# untitled.net
KiCad netlist of a schematic drawn in EAGLE
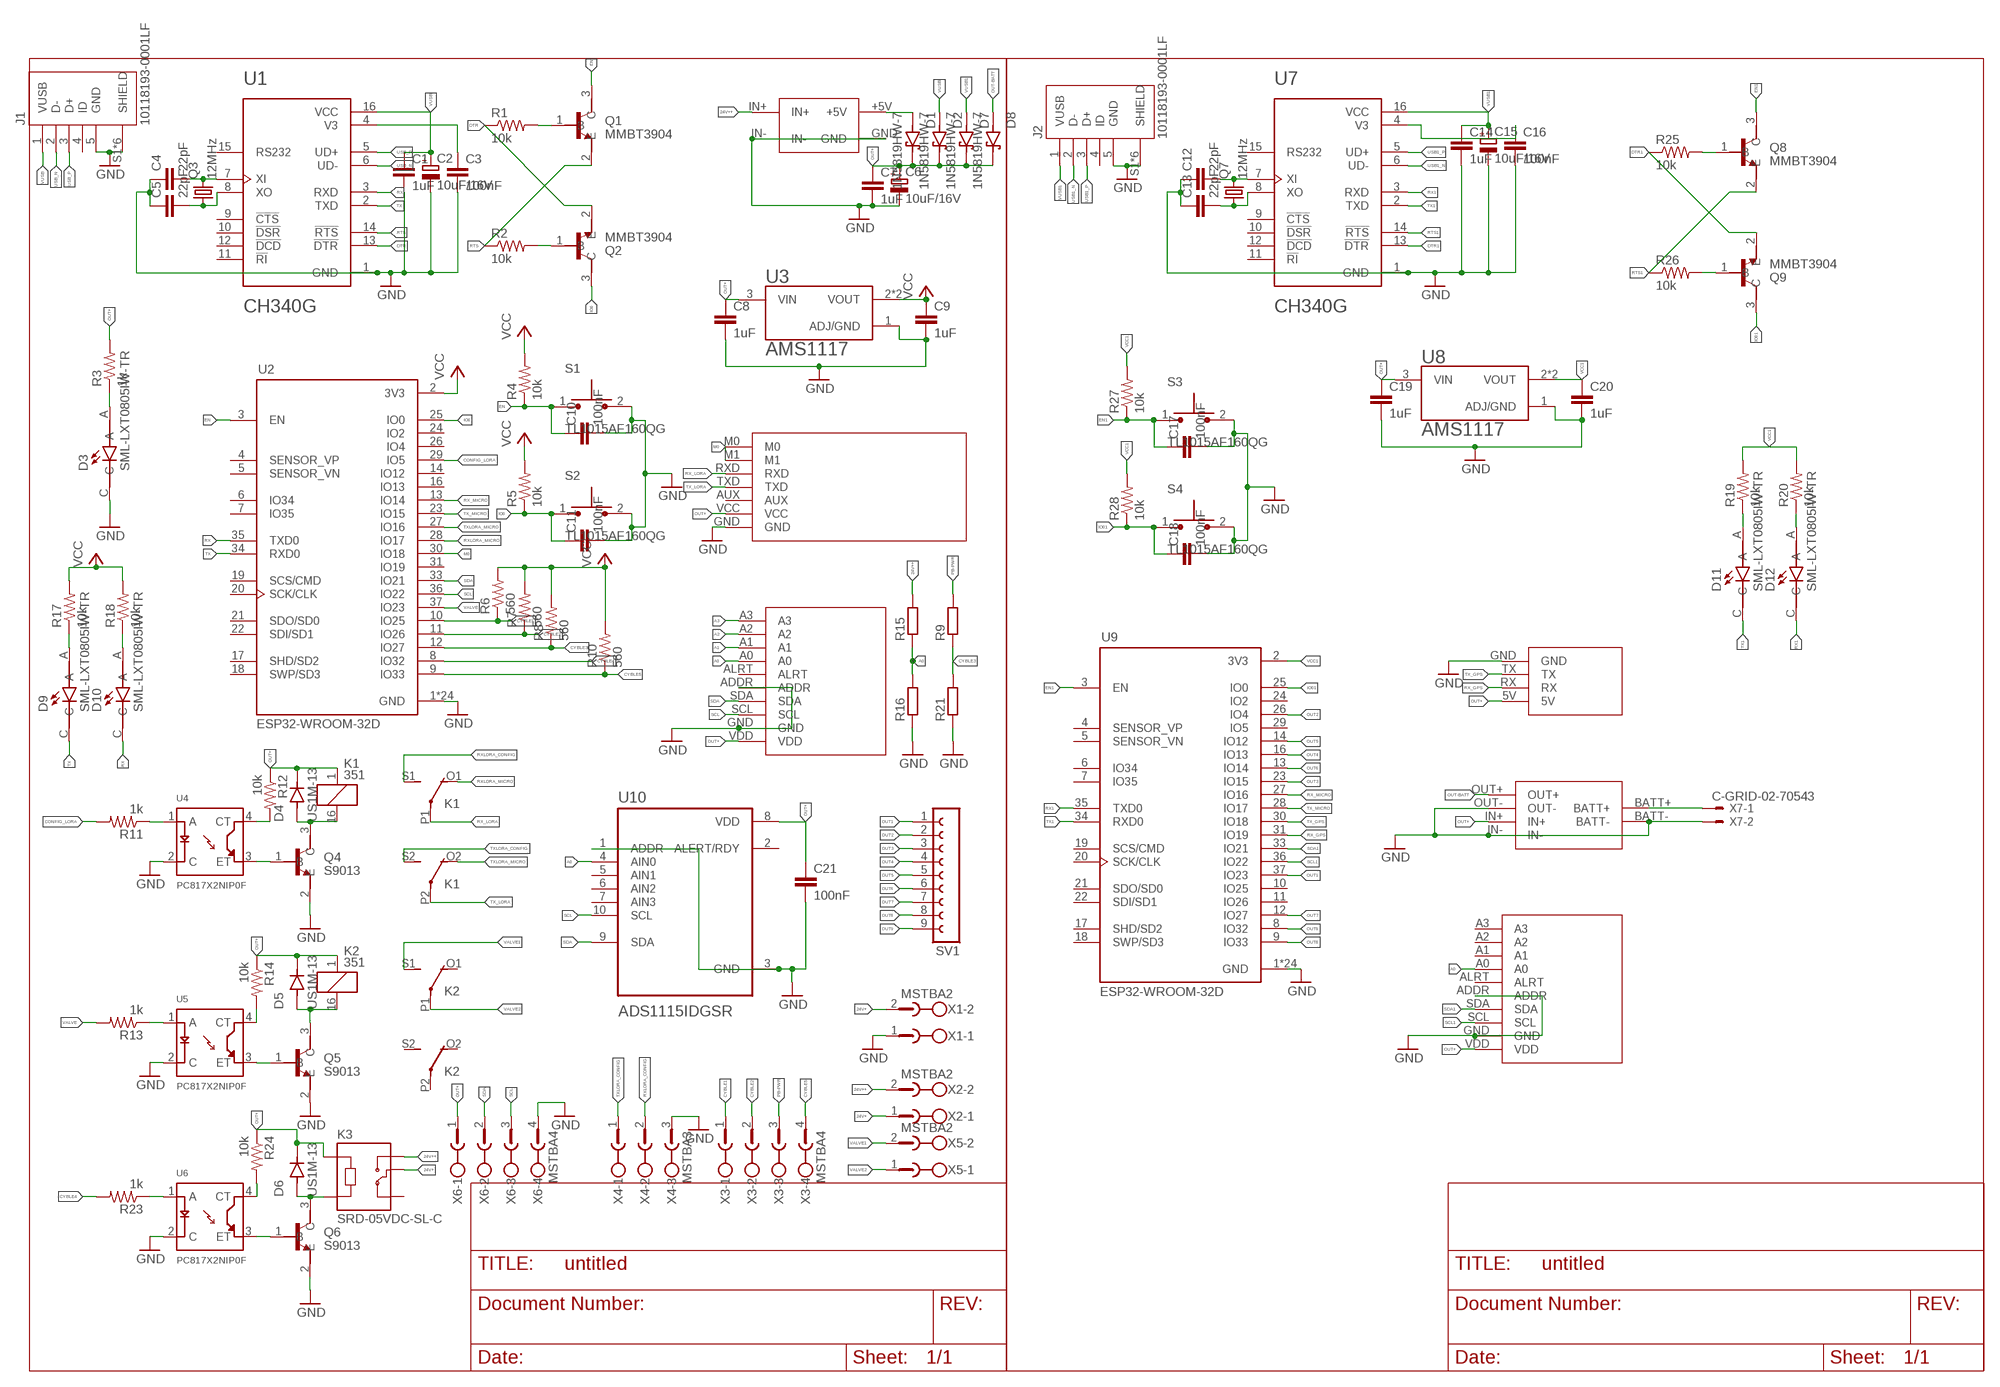
[diagram p0: schematic, sheet 1]

(export (version "E")
  (design (tool "Eeschema 10.0.6"))
  (components
    (comp (ref "ADS1")
      (value "ADS1115")
      (footprint "eagle-import:ADS1115")
      (libsource (lib "eagle-import") (part "ADS1115"))
    )
    (comp (ref "ADS2")
      (value "ADS1115")
      (footprint "eagle-import:ADS1115")
      (libsource (lib "eagle-import") (part "ADS1115"))
    )
    (comp (ref "C1")
      (value "1uF")
      (footprint "eagle-import:C0805K")
      (libsource (lib "eagle-import") (part "C-EUC0805K"))
    )
    (comp (ref "C2")
      (value "10uF/16V")
      (footprint "eagle-import:153CLV-0505")
      (libsource (lib "eagle-import") (part "CPOL-EU153CLV-0505"))
    )
    (comp (ref "C3")
      (value "100nF")
      (footprint "eagle-import:C0805K")
      (libsource (lib "eagle-import") (part "C-EUC0805K"))
    )
    (comp (ref "C4")
      (value "22pF")
      (footprint "eagle-import:C0805K")
      (libsource (lib "eagle-import") (part "C-EUC0805K"))
    )
    (comp (ref "C5")
      (value "22pF")
      (footprint "eagle-import:C0805K")
      (libsource (lib "eagle-import") (part "C-EUC0805K"))
    )
    (comp (ref "C6")
      (value "10uF/16V")
      (footprint "eagle-import:153CLV-0505")
      (libsource (lib "eagle-import") (part "CPOL-EU153CLV-0505"))
    )
    (comp (ref "C7")
      (value "1uF")
      (footprint "eagle-import:C0805K")
      (libsource (lib "eagle-import") (part "C-EUC0805K"))
    )
    (comp (ref "C8")
      (value "1uF")
      (footprint "eagle-import:C0805K")
      (libsource (lib "eagle-import") (part "C-EUC0805K"))
    )
    (comp (ref "C9")
      (value "1uF")
      (footprint "eagle-import:C0805K")
      (libsource (lib "eagle-import") (part "C-EUC0805K"))
    )
    (comp (ref "C10")
      (value "100nF")
      (footprint "eagle-import:C0805K")
      (libsource (lib "eagle-import") (part "C-EUC0805K"))
    )
    (comp (ref "C11")
      (value "100nF")
      (footprint "eagle-import:C0805K")
      (libsource (lib "eagle-import") (part "C-EUC0805K"))
    )
    (comp (ref "C12")
      (value "22pF")
      (footprint "eagle-import:C0805K")
      (libsource (lib "eagle-import") (part "C-EUC0805K"))
    )
    (comp (ref "C13")
      (value "22pF")
      (footprint "eagle-import:C0805K")
      (libsource (lib "eagle-import") (part "C-EUC0805K"))
    )
    (comp (ref "C14")
      (value "1uF")
      (footprint "eagle-import:C0805K")
      (libsource (lib "eagle-import") (part "C-EUC0805K"))
    )
    (comp (ref "C15")
      (value "10uF/16V")
      (footprint "eagle-import:153CLV-0505")
      (libsource (lib "eagle-import") (part "CPOL-EU153CLV-0505"))
    )
    (comp (ref "C16")
      (value "100nF")
      (footprint "eagle-import:C0805K")
      (libsource (lib "eagle-import") (part "C-EUC0805K"))
    )
    (comp (ref "C17")
      (value "100nF")
      (footprint "eagle-import:C0805K")
      (libsource (lib "eagle-import") (part "C-EUC0805K"))
    )
    (comp (ref "C18")
      (value "100nF")
      (footprint "eagle-import:C0805K")
      (libsource (lib "eagle-import") (part "C-EUC0805K"))
    )
    (comp (ref "C19")
      (value "1uF")
      (footprint "eagle-import:C0805K")
      (libsource (lib "eagle-import") (part "C-EUC0805K"))
    )
    (comp (ref "C20")
      (value "1uF")
      (footprint "eagle-import:C0805K")
      (libsource (lib "eagle-import") (part "C-EUC0805K"))
    )
    (comp (ref "C21")
      (value "100nF")
      (footprint "eagle-import:C0805K")
      (libsource (lib "eagle-import") (part "C-EUC0805K"))
    )
    (comp (ref "D1")
      (value "1N5819HW-7")
      (footprint "eagle-import:SOD3715X145N")
      (fields (field (name "MF") "Diodes Inc."))
      (libsource (lib "eagle-import") (part "1N5819HW-7"))
    )
    (comp (ref "D2")
      (value "1N5819HW-7")
      (footprint "eagle-import:SOD3715X145N")
      (fields (field (name "MF") "Diodes Inc."))
      (libsource (lib "eagle-import") (part "1N5819HW-7"))
    )
    (comp (ref "D3")
      (value "SML-LXT0805IW-TR")
      (footprint "eagle-import:LEDC2012X120N")
      (fields (field (name "MF") "Lumex Opto/Components"))
      (libsource (lib "eagle-import") (part "SML-LXT0805IW-TR"))
    )
    (comp (ref "D4")
      (value "US1M-13")
      (footprint "eagle-import:DIOM5226X240N")
      (fields (field (name "MF") "Diodes Incorporated"))
      (libsource (lib "eagle-import") (part "US1M-13"))
    )
    (comp (ref "D5")
      (value "US1M-13")
      (footprint "eagle-import:DIOM5226X240N")
      (fields (field (name "MF") "Diodes Incorporated"))
      (libsource (lib "eagle-import") (part "US1M-13"))
    )
    (comp (ref "D6")
      (value "US1M-13")
      (footprint "eagle-import:DIOM5226X240N")
      (fields (field (name "MF") "Diodes Incorporated"))
      (libsource (lib "eagle-import") (part "US1M-13"))
    )
    (comp (ref "D7")
      (value "1N5819HW-7")
      (footprint "eagle-import:SOD3715X145N")
      (fields (field (name "MF") "Diodes Inc."))
      (libsource (lib "eagle-import") (part "1N5819HW-7"))
    )
    (comp (ref "D8")
      (value "1N5819HW-7")
      (footprint "eagle-import:SOD3715X145N")
      (fields (field (name "MF") "Diodes Inc."))
      (libsource (lib "eagle-import") (part "1N5819HW-7"))
    )
    (comp (ref "D9")
      (value "SML-LXT0805IW-TR")
      (footprint "eagle-import:LEDC2012X120N")
      (fields (field (name "MF") "Lumex Opto/Components"))
      (libsource (lib "eagle-import") (part "SML-LXT0805IW-TR"))
    )
    (comp (ref "D10")
      (value "SML-LXT0805IW-TR")
      (footprint "eagle-import:LEDC2012X120N")
      (fields (field (name "MF") "Lumex Opto/Components"))
      (libsource (lib "eagle-import") (part "SML-LXT0805IW-TR"))
    )
    (comp (ref "D11")
      (value "SML-LXT0805IW-TR")
      (footprint "eagle-import:LEDC2012X120N")
      (fields (field (name "MF") "Lumex Opto/Components"))
      (libsource (lib "eagle-import") (part "SML-LXT0805IW-TR"))
    )
    (comp (ref "D12")
      (value "SML-LXT0805IW-TR")
      (footprint "eagle-import:LEDC2012X120N")
      (fields (field (name "MF") "Lumex Opto/Components"))
      (libsource (lib "eagle-import") (part "SML-LXT0805IW-TR"))
    )
    (comp (ref "EBYTEE220-900T22D1")
      (value "EBYTEE220-900T22D")
      (footprint "eagle-import:EBYTEE220-900T22D")
      (libsource (lib "eagle-import") (part "EBYTEE220-900T22D"))
    )
    (comp (ref "J1")
      (value "10118193-0001LF")
      (footprint "eagle-import:FCI_10118193-0001LF")
      (fields (field (name "MF") "FCI"))
      (libsource (lib "eagle-import") (part "10118193-0001LF"))
    )
    (comp (ref "J2")
      (value "10118193-0001LF")
      (footprint "eagle-import:FCI_10118193-0001LF")
      (fields (field (name "MF") "FCI"))
      (libsource (lib "eagle-import") (part "10118193-0001LF"))
    )
    (comp (ref "K1")
      (value "351")
      (footprint "eagle-import:351")
      (libsource (lib "eagle-import") (part "351"))
    )
    (comp (ref "K2")
      (value "351")
      (footprint "eagle-import:351")
      (libsource (lib "eagle-import") (part "351"))
    )
    (comp (ref "K3")
      (value "SRD-05VDC-SL-C")
      (footprint "eagle-import:RELAY_SRD-05VDC-SL-C")
      (fields (field (name "MF") "Songle Relay"))
      (libsource (lib "eagle-import") (part "SRD-05VDC-SL-C"))
    )
    (comp (ref "MODUL-BATT1")
      (value "MODUL-BATT")
      (footprint "eagle-import:MODUL-BATT")
      (libsource (lib "eagle-import") (part "MODUL-BATT"))
    )
    (comp (ref "NEO-6MGPS1")
      (value "NEO-6MGPS")
      (footprint "eagle-import:NEO-6MGPS")
      (libsource (lib "eagle-import") (part "NEO-6MGPS"))
    )
    (comp (ref "Q1")
      (value "MMBT3904")
      (footprint "eagle-import:SOT95P240X120-3N")
      (fields (field (name "MF") "ON Semiconductor"))
      (libsource (lib "eagle-import") (part "MMBT3904"))
    )
    (comp (ref "Q2")
      (value "MMBT3904")
      (footprint "eagle-import:SOT95P240X120-3N")
      (fields (field (name "MF") "ON Semiconductor"))
      (libsource (lib "eagle-import") (part "MMBT3904"))
    )
    (comp (ref "Q3")
      (value "12MHz")
      (footprint "eagle-import:SM49")
      (libsource (lib "eagle-import") (part "CRYSTALSM49"))
    )
    (comp (ref "Q4")
      (value "S9013")
      (footprint "eagle-import:SOT95P240X120-3N")
      (fields (field (name "MF") "JCET"))
      (libsource (lib "eagle-import") (part "S9013"))
    )
    (comp (ref "Q5")
      (value "S9013")
      (footprint "eagle-import:SOT95P240X120-3N")
      (fields (field (name "MF") "JCET"))
      (libsource (lib "eagle-import") (part "S9013"))
    )
    (comp (ref "Q6")
      (value "S9013")
      (footprint "eagle-import:SOT95P240X120-3N")
      (fields (field (name "MF") "JCET"))
      (libsource (lib "eagle-import") (part "S9013"))
    )
    (comp (ref "Q7")
      (value "12MHz")
      (footprint "eagle-import:SM49")
      (libsource (lib "eagle-import") (part "CRYSTALSM49"))
    )
    (comp (ref "Q8")
      (value "MMBT3904")
      (footprint "eagle-import:SOT95P240X120-3N")
      (fields (field (name "MF") "ON Semiconductor"))
      (libsource (lib "eagle-import") (part "MMBT3904"))
    )
    (comp (ref "Q9")
      (value "MMBT3904")
      (footprint "eagle-import:SOT95P240X120-3N")
      (fields (field (name "MF") "ON Semiconductor"))
      (libsource (lib "eagle-import") (part "MMBT3904"))
    )
    (comp (ref "R1")
      (value "10k")
      (footprint "eagle-import:M0805")
      (libsource (lib "eagle-import") (part "R-US_M0805"))
    )
    (comp (ref "R2")
      (value "10k")
      (footprint "eagle-import:M0805")
      (libsource (lib "eagle-import") (part "R-US_M0805"))
    )
    (comp (ref "R3")
      (value "1k")
      (footprint "eagle-import:M0805")
      (libsource (lib "eagle-import") (part "R-US_M0805"))
    )
    (comp (ref "R4")
      (value "10k")
      (footprint "eagle-import:M0805")
      (libsource (lib "eagle-import") (part "R-US_M0805"))
    )
    (comp (ref "R5")
      (value "10k")
      (footprint "eagle-import:M0805")
      (libsource (lib "eagle-import") (part "R-US_M0805"))
    )
    (comp (ref "R6")
      (value "560")
      (footprint "eagle-import:M0805")
      (libsource (lib "eagle-import") (part "R-US_M0805"))
    )
    (comp (ref "R7")
      (value "560")
      (footprint "eagle-import:M0805")
      (libsource (lib "eagle-import") (part "R-US_M0805"))
    )
    (comp (ref "R8")
      (value "560")
      (footprint "eagle-import:M0805")
      (libsource (lib "eagle-import") (part "R-US_M0805"))
    )
    (comp (ref "R9")
      (value "R-EU_0207/12")
      (footprint "eagle-import:0207_12")
      (libsource (lib "eagle-import") (part "R-EU_0207/12"))
    )
    (comp (ref "R10")
      (value "560")
      (footprint "eagle-import:M0805")
      (libsource (lib "eagle-import") (part "R-US_M0805"))
    )
    (comp (ref "R11")
      (value "1k")
      (footprint "eagle-import:M0805")
      (libsource (lib "eagle-import") (part "R-US_M0805"))
    )
    (comp (ref "R12")
      (value "10k")
      (footprint "eagle-import:M0805")
      (libsource (lib "eagle-import") (part "R-US_M0805"))
    )
    (comp (ref "R13")
      (value "1k")
      (footprint "eagle-import:M0805")
      (libsource (lib "eagle-import") (part "R-US_M0805"))
    )
    (comp (ref "R14")
      (value "10k")
      (footprint "eagle-import:M0805")
      (libsource (lib "eagle-import") (part "R-US_M0805"))
    )
    (comp (ref "R15")
      (value "R-EU_0207/12")
      (footprint "eagle-import:0207_12")
      (libsource (lib "eagle-import") (part "R-EU_0207/12"))
    )
    (comp (ref "R16")
      (value "R-EU_0207/12")
      (footprint "eagle-import:0207_12")
      (libsource (lib "eagle-import") (part "R-EU_0207/12"))
    )
    (comp (ref "R17")
      (value "10k")
      (footprint "eagle-import:M0805")
      (libsource (lib "eagle-import") (part "R-US_M0805"))
    )
    (comp (ref "R18")
      (value "10k")
      (footprint "eagle-import:M0805")
      (libsource (lib "eagle-import") (part "R-US_M0805"))
    )
    (comp (ref "R19")
      (value "10k")
      (footprint "eagle-import:M0805")
      (libsource (lib "eagle-import") (part "R-US_M0805"))
    )
    (comp (ref "R20")
      (value "10k")
      (footprint "eagle-import:M0805")
      (libsource (lib "eagle-import") (part "R-US_M0805"))
    )
    (comp (ref "R21")
      (value "R-EU_0207/12")
      (footprint "eagle-import:0207_12")
      (libsource (lib "eagle-import") (part "R-EU_0207/12"))
    )
    (comp (ref "R23")
      (value "1k")
      (footprint "eagle-import:M0805")
      (libsource (lib "eagle-import") (part "R-US_M0805"))
    )
    (comp (ref "R24")
      (value "10k")
      (footprint "eagle-import:M0805")
      (libsource (lib "eagle-import") (part "R-US_M0805"))
    )
    (comp (ref "R25")
      (value "10k")
      (footprint "eagle-import:M0805")
      (libsource (lib "eagle-import") (part "R-US_M0805"))
    )
    (comp (ref "R26")
      (value "10k")
      (footprint "eagle-import:M0805")
      (libsource (lib "eagle-import") (part "R-US_M0805"))
    )
    (comp (ref "R27")
      (value "10k")
      (footprint "eagle-import:M0805")
      (libsource (lib "eagle-import") (part "R-US_M0805"))
    )
    (comp (ref "R28")
      (value "10k")
      (footprint "eagle-import:M0805")
      (libsource (lib "eagle-import") (part "R-US_M0805"))
    )
    (comp (ref "S1")
      (value "TL1015AF160QG")
      (footprint "eagle-import:SW_TL1015AF160QG")
      (fields (field (name "MF") "E-Switch"))
      (libsource (lib "eagle-import") (part "TL1015AF160QG"))
    )
    (comp (ref "S2")
      (value "TL1015AF160QG")
      (footprint "eagle-import:SW_TL1015AF160QG")
      (fields (field (name "MF") "E-Switch"))
      (libsource (lib "eagle-import") (part "TL1015AF160QG"))
    )
    (comp (ref "S3")
      (value "TL1015AF160QG")
      (footprint "eagle-import:SW_TL1015AF160QG")
      (fields (field (name "MF") "E-Switch"))
      (libsource (lib "eagle-import") (part "TL1015AF160QG"))
    )
    (comp (ref "S4")
      (value "TL1015AF160QG")
      (footprint "eagle-import:SW_TL1015AF160QG")
      (fields (field (name "MF") "E-Switch"))
      (libsource (lib "eagle-import") (part "TL1015AF160QG"))
    )
    (comp (ref "SUPER-STEPDOWN1")
      (value "SUPER-STEPDOWN")
      (footprint "eagle-import:SUPER-STEPDOWN")
      (libsource (lib "eagle-import") (part "SUPER-STEPDOWN"))
    )
    (comp (ref "SV1")
      (value "FE09-1")
      (footprint "eagle-import:FE09")
      (libsource (lib "eagle-import") (part "FE09-1"))
    )
    (comp (ref "U1")
      (value "CH340G")
      (footprint "eagle-import:SOIC127P600X180-16N")
      (fields (field (name "MF") "WCH") (field (name "MP") "Ch340G"))
      (libsource (lib "eagle-import") (part "CH340G"))
    )
    (comp (ref "U2")
      (value "ESP32-WROOM-32D")
      (footprint "eagle-import:MODULE_ESP32-WROOM-32D")
      (fields (field (name "MF") "Espressif Systems"))
      (libsource (lib "eagle-import") (part "ESP32-WROOM-32D"))
    )
    (comp (ref "U3")
      (value "AMS1117")
      (footprint "eagle-import:SOT229P700X180-4N")
      (fields (field (name "MF") "Advanced Monolithic Systems"))
      (libsource (lib "eagle-import") (part "AMS1117"))
    )
    (comp (ref "U4")
      (value "PC817X2NIP0F")
      (footprint "eagle-import:SOT254P975X400-4N")
      (fields (field (name "MF") "Sharp Microelectronics"))
      (libsource (lib "eagle-import") (part "PC817X2NIP0F"))
    )
    (comp (ref "U5")
      (value "PC817X2NIP0F")
      (footprint "eagle-import:SOT254P975X400-4N")
      (fields (field (name "MF") "Sharp Microelectronics"))
      (libsource (lib "eagle-import") (part "PC817X2NIP0F"))
    )
    (comp (ref "U6")
      (value "PC817X2NIP0F")
      (footprint "eagle-import:SOT254P975X400-4N")
      (fields (field (name "MF") "Sharp Microelectronics"))
      (libsource (lib "eagle-import") (part "PC817X2NIP0F"))
    )
    (comp (ref "U7")
      (value "CH340G")
      (footprint "eagle-import:SOIC127P600X180-16N")
      (fields (field (name "MF") "WCH") (field (name "MP") "Ch340G"))
      (libsource (lib "eagle-import") (part "CH340G"))
    )
    (comp (ref "U8")
      (value "AMS1117")
      (footprint "eagle-import:SOT229P700X180-4N")
      (fields (field (name "MF") "Advanced Monolithic Systems"))
      (libsource (lib "eagle-import") (part "AMS1117"))
    )
    (comp (ref "U9")
      (value "ESP32-WROOM-32D")
      (footprint "eagle-import:MODULE_ESP32-WROOM-32D")
      (fields (field (name "MF") "Espressif Systems"))
      (libsource (lib "eagle-import") (part "ESP32-WROOM-32D"))
    )
    (comp (ref "U10")
      (value "ADS1115IDGSR")
      (footprint "eagle-import:SOP50P490X110-10N")
      (fields (field (name "MF") "Texas Instruments"))
      (libsource (lib "eagle-import") (part "ADS1115IDGSR"))
    )
    (comp (ref "X1")
      (value "MSTBA2")
      (footprint "eagle-import:MSTBA2")
      (fields (field (name "MF") "FARNELL") (field (name "MPN") "1757242"))
      (libsource (lib "eagle-import") (part "MSTBA2"))
    )
    (comp (ref "X2")
      (value "MSTBA2")
      (footprint "eagle-import:MSTBA2")
      (fields (field (name "MF") "FARNELL") (field (name "MPN") "1757242"))
      (libsource (lib "eagle-import") (part "MSTBA2"))
    )
    (comp (ref "X3")
      (value "MSTBA4")
      (footprint "eagle-import:MSTBA4")
      (fields (field (name "MF") "FARNELL") (field (name "MPN") "1757268"))
      (libsource (lib "eagle-import") (part "MSTBA4"))
    )
    (comp (ref "X4")
      (value "MSTBA3")
      (footprint "eagle-import:MSTBA3")
      (fields (field (name "MF") "FARNELL") (field (name "MPN") "1757255"))
      (libsource (lib "eagle-import") (part "MSTBA3"))
    )
    (comp (ref "X5")
      (value "MSTBA2")
      (footprint "eagle-import:MSTBA2")
      (fields (field (name "MF") "FARNELL") (field (name "MPN") "1757242"))
      (libsource (lib "eagle-import") (part "MSTBA2"))
    )
    (comp (ref "X6")
      (value "MSTBA4")
      (footprint "eagle-import:MSTBA4")
      (fields (field (name "MF") "FARNELL") (field (name "MPN") "1757268"))
      (libsource (lib "eagle-import") (part "MSTBA4"))
    )
    (comp (ref "X7")
      (value "C-GRID-02-70543")
      (footprint "eagle-import:70543-02")
      (fields (field (name "MF") "MOLEX"))
      (libsource (lib "eagle-import") (part "C-GRID-02-70543"))
    )
  )
  (nets
    (net (code "1") (name "24V+") (class "Default")
      (node (ref "K3") (pin "COM") (pinfunction "COM_COM") (pintype "passive"))
      (node (ref "X1") (pin "2") (pinfunction "1_2") (pintype "passive"))
      (node (ref "X2") (pin "1") (pinfunction "1_1") (pintype "passive"))
    )
    (net (code "2") (name "24V++") (class "Default")
      (node (ref "K3") (pin "NO") (pinfunction "NO_NO") (pintype "passive"))
      (node (ref "R15") (pin "2") (pinfunction "2_2") (pintype "passive"))
      (node (ref "SUPER-STEPDOWN1") (pin "IN+") (pinfunction "IN+_IN+") (pintype "bidirectional"))
      (node (ref "X2") (pin "2") (pinfunction "1_2") (pintype "passive"))
    )
    (net (code "3") (name "A0") (class "Default")
      (node (ref "ADS1") (pin "A0") (pinfunction "A0_A0") (pintype "bidirectional"))
      (node (ref "ADS2") (pin "A0") (pinfunction "A0_A0") (pintype "bidirectional"))
      (node (ref "R15") (pin "1") (pinfunction "1_1") (pintype "passive"))
      (node (ref "R16") (pin "2") (pinfunction "2_2") (pintype "passive"))
      (node (ref "U10") (pin "4") (pinfunction "AIN0_4") (pintype "input"))
    )
    (net (code "4") (name "A1") (class "Default")
      (node (ref "ADS1") (pin "A1") (pinfunction "A1_A1") (pintype "bidirectional"))
    )
    (net (code "5") (name "A2") (class "Default")
      (node (ref "ADS1") (pin "A2") (pinfunction "A2_A2") (pintype "bidirectional"))
    )
    (net (code "6") (name "A3") (class "Default")
      (node (ref "ADS1") (pin "A3") (pinfunction "A3_A3") (pintype "bidirectional"))
    )
    (net (code "7") (name "CONFIG_LORA") (class "Default")
      (node (ref "R11") (pin "2") (pinfunction "2_2") (pintype "passive"))
      (node (ref "U2") (pin "29") (pinfunction "IO5_29") (pintype "bidirectional"))
    )
    (net (code "8") (name "CYBLE1") (class "Default")
      (node (ref "R6") (pin "1") (pinfunction "1_1") (pintype "passive"))
      (node (ref "U2") (pin "10") (pinfunction "IO25_10") (pintype "bidirectional"))
      (node (ref "X3") (pin "1") (pinfunction "1_1") (pintype "passive"))
    )
    (net (code "9") (name "CYBLE2") (class "Default")
      (node (ref "R7") (pin "1") (pinfunction "1_1") (pintype "passive"))
      (node (ref "U2") (pin "11") (pinfunction "IO26_11") (pintype "bidirectional"))
      (node (ref "X3") (pin "2") (pinfunction "1_2") (pintype "passive"))
    )
    (net (code "10") (name "CYBLE3") (class "Default")
      (node (ref "R21") (pin "2") (pinfunction "2_2") (pintype "passive"))
      (node (ref "R8") (pin "1") (pinfunction "1_1") (pintype "passive"))
      (node (ref "R9") (pin "1") (pinfunction "1_1") (pintype "passive"))
      (node (ref "U2") (pin "12") (pinfunction "IO27_12") (pintype "bidirectional"))
    )
    (net (code "11") (name "CYBLE4") (class "Default")
      (node (ref "R23") (pin "2") (pinfunction "2_2") (pintype "passive"))
      (node (ref "U2") (pin "8") (pinfunction "IO32_8") (pintype "bidirectional"))
    )
    (net (code "12") (name "CYBLE5") (class "Default")
      (node (ref "R10") (pin "1") (pinfunction "1_1") (pintype "passive"))
      (node (ref "U2") (pin "9") (pinfunction "IO33_9") (pintype "bidirectional"))
      (node (ref "X3") (pin "4") (pinfunction "1_4") (pintype "passive"))
    )
    (net (code "13") (name "DTR") (class "Default")
      (node (ref "Q2") (pin "2") (pinfunction "E_2") (pintype "passive"))
      (node (ref "R1") (pin "1") (pinfunction "1_1") (pintype "passive"))
      (node (ref "U1") (pin "13") (pinfunction "~{DTR}_13") (pintype "output"))
    )
    (net (code "14") (name "DTR1") (class "Default")
      (node (ref "Q9") (pin "2") (pinfunction "E_2") (pintype "passive"))
      (node (ref "R25") (pin "1") (pinfunction "1_1") (pintype "passive"))
      (node (ref "U7") (pin "13") (pinfunction "~{DTR}_13") (pintype "output"))
    )
    (net (code "15") (name "EN") (class "Default")
      (node (ref "C10") (pin "1") (pinfunction "1_1") (pintype "passive"))
      (node (ref "Q1") (pin "3") (pinfunction "C_3") (pintype "passive"))
      (node (ref "R4") (pin "1") (pinfunction "1_1") (pintype "passive"))
      (node (ref "S1") (pin "1") (pinfunction "1_1") (pintype "passive"))
      (node (ref "U2") (pin "3") (pinfunction "EN_3") (pintype "input"))
    )
    (net (code "16") (name "EN1") (class "Default")
      (node (ref "C17") (pin "1") (pinfunction "1_1") (pintype "passive"))
      (node (ref "Q8") (pin "3") (pinfunction "C_3") (pintype "passive"))
      (node (ref "R27") (pin "1") (pinfunction "1_1") (pintype "passive"))
      (node (ref "S3") (pin "1") (pinfunction "1_1") (pintype "passive"))
      (node (ref "U9") (pin "3") (pinfunction "EN_3") (pintype "input"))
    )
    (net (code "17") (name "GND") (class "Default")
      (node (ref "ADS1") (pin "ADDR") (pinfunction "ADDR_ADDR") (pintype "bidirectional"))
      (node (ref "ADS1") (pin "GND") (pinfunction "GND_GND") (pintype "bidirectional"))
      (node (ref "ADS2") (pin "ADDR") (pinfunction "ADDR_ADDR") (pintype "bidirectional"))
      (node (ref "ADS2") (pin "GND") (pinfunction "GND_GND") (pintype "bidirectional"))
      (node (ref "C1") (pin "2") (pinfunction "2_2") (pintype "passive"))
      (node (ref "C10") (pin "2") (pinfunction "2_2") (pintype "passive"))
      (node (ref "C11") (pin "2") (pinfunction "2_2") (pintype "passive"))
      (node (ref "C12") (pin "1") (pinfunction "1_1") (pintype "passive"))
      (node (ref "C13") (pin "1") (pinfunction "1_1") (pintype "passive"))
      (node (ref "C14") (pin "2") (pinfunction "2_2") (pintype "passive"))
      (node (ref "C15") (pin "-") (pinfunction "-_-") (pintype "passive"))
      (node (ref "C16") (pin "2") (pinfunction "2_2") (pintype "passive"))
      (node (ref "C17") (pin "2") (pinfunction "2_2") (pintype "passive"))
      (node (ref "C18") (pin "2") (pinfunction "2_2") (pintype "passive"))
      (node (ref "C19") (pin "2") (pinfunction "2_2") (pintype "passive"))
      (node (ref "C2") (pin "-") (pinfunction "-_-") (pintype "passive"))
      (node (ref "C20") (pin "2") (pinfunction "2_2") (pintype "passive"))
      (node (ref "C21") (pin "2") (pinfunction "2_2") (pintype "passive"))
      (node (ref "C3") (pin "2") (pinfunction "2_2") (pintype "passive"))
      (node (ref "C4") (pin "1") (pinfunction "1_1") (pintype "passive"))
      (node (ref "C5") (pin "1") (pinfunction "1_1") (pintype "passive"))
      (node (ref "C6") (pin "-") (pinfunction "-_-") (pintype "passive"))
      (node (ref "C7") (pin "2") (pinfunction "2_2") (pintype "passive"))
      (node (ref "C8") (pin "2") (pinfunction "2_2") (pintype "passive"))
      (node (ref "C9") (pin "2") (pinfunction "2_2") (pintype "passive"))
      (node (ref "D3") (pin "C") (pinfunction "C_C") (pintype "passive"))
      (node (ref "EBYTEE220-900T22D1") (pin "GND") (pinfunction "GND_GND") (pintype "bidirectional"))
      (node (ref "J1") (pin "5") (pinfunction "GND_5") (pintype "passive"))
      (node (ref "J1") (pin "S1") (pinfunction "SHIELD_S1") (pintype "passive"))
      (node (ref "J1") (pin "S2") (pinfunction "SHIELD_S2") (pintype "passive"))
      (node (ref "J1") (pin "S3") (pinfunction "SHIELD_S3") (pintype "passive"))
      (node (ref "J1") (pin "S4") (pinfunction "SHIELD_S4") (pintype "passive"))
      (node (ref "J1") (pin "S5") (pinfunction "SHIELD_S5") (pintype "passive"))
      (node (ref "J1") (pin "S6") (pinfunction "SHIELD_S6") (pintype "passive"))
      (node (ref "J2") (pin "5") (pinfunction "GND_5") (pintype "passive"))
      (node (ref "J2") (pin "S1") (pinfunction "SHIELD_S1") (pintype "passive"))
      (node (ref "J2") (pin "S2") (pinfunction "SHIELD_S2") (pintype "passive"))
      (node (ref "J2") (pin "S3") (pinfunction "SHIELD_S3") (pintype "passive"))
      (node (ref "J2") (pin "S4") (pinfunction "SHIELD_S4") (pintype "passive"))
      (node (ref "J2") (pin "S5") (pinfunction "SHIELD_S5") (pintype "passive"))
      (node (ref "J2") (pin "S6") (pinfunction "SHIELD_S6") (pintype "passive"))
      (node (ref "MODUL-BATT1") (pin "BATT-") (pinfunction "BATT-_BATT-") (pintype "bidirectional"))
      (node (ref "MODUL-BATT1") (pin "IN-") (pinfunction "IN-_IN-") (pintype "bidirectional"))
      (node (ref "MODUL-BATT1") (pin "OUT-") (pinfunction "OUT-_OUT-") (pintype "bidirectional"))
      (node (ref "NEO-6MGPS1") (pin "GND") (pinfunction "GND_GND") (pintype "bidirectional"))
      (node (ref "Q4") (pin "2") (pinfunction "E_2") (pintype "passive"))
      (node (ref "Q5") (pin "2") (pinfunction "E_2") (pintype "passive"))
      (node (ref "Q6") (pin "2") (pinfunction "E_2") (pintype "passive"))
      (node (ref "R16") (pin "1") (pinfunction "1_1") (pintype "passive"))
      (node (ref "R21") (pin "1") (pinfunction "1_1") (pintype "passive"))
      (node (ref "S1") (pin "2") (pinfunction "2_2") (pintype "passive"))
      (node (ref "S2") (pin "2") (pinfunction "2_2") (pintype "passive"))
      (node (ref "S3") (pin "2") (pinfunction "2_2") (pintype "passive"))
      (node (ref "S4") (pin "2") (pinfunction "2_2") (pintype "passive"))
      (node (ref "SUPER-STEPDOWN1") (pin "GND") (pinfunction "GND_GND") (pintype "bidirectional"))
      (node (ref "SUPER-STEPDOWN1") (pin "IN-") (pinfunction "IN-_IN-") (pintype "bidirectional"))
      (node (ref "U1") (pin "1") (pinfunction "GND_1") (pintype "power_in"))
      (node (ref "U10") (pin "1") (pinfunction "ADDR_1") (pintype "input"))
      (node (ref "U10") (pin "3") (pinfunction "GND_3") (pintype "power_in"))
      (node (ref "U2") (pin "1") (pinfunction "GND_1") (pintype "power_in"))
      (node (ref "U2") (pin "15") (pinfunction "GND_15") (pintype "power_in"))
      (node (ref "U2") (pin "38") (pinfunction "GND_38") (pintype "power_in"))
      (node (ref "U2") (pin "39_1") (pinfunction "GND_39_1") (pintype "power_in"))
      (node (ref "U2") (pin "39_10") (pinfunction "GND_39_10") (pintype "power_in"))
      (node (ref "U2") (pin "39_11") (pinfunction "GND_39_11") (pintype "power_in"))
      (node (ref "U2") (pin "39_12") (pinfunction "GND_39_12") (pintype "power_in"))
      (node (ref "U2") (pin "39_13") (pinfunction "GND_39_13") (pintype "power_in"))
      (node (ref "U2") (pin "39_14") (pinfunction "GND_39_14") (pintype "power_in"))
      (node (ref "U2") (pin "39_15") (pinfunction "GND_39_15") (pintype "power_in"))
      (node (ref "U2") (pin "39_16") (pinfunction "GND_39_16") (pintype "power_in"))
      (node (ref "U2") (pin "39_17") (pinfunction "GND_39_17") (pintype "power_in"))
      (node (ref "U2") (pin "39_18") (pinfunction "GND_39_18") (pintype "power_in"))
      (node (ref "U2") (pin "39_19") (pinfunction "GND_39_19") (pintype "power_in"))
      (node (ref "U2") (pin "39_2") (pinfunction "GND_39_2") (pintype "power_in"))
      (node (ref "U2") (pin "39_20") (pinfunction "GND_39_20") (pintype "power_in"))
      (node (ref "U2") (pin "39_21") (pinfunction "GND_39_21") (pintype "power_in"))
      (node (ref "U2") (pin "39_3") (pinfunction "GND_39_3") (pintype "power_in"))
      (node (ref "U2") (pin "39_4") (pinfunction "GND_39_4") (pintype "power_in"))
      (node (ref "U2") (pin "39_5") (pinfunction "GND_39_5") (pintype "power_in"))
      (node (ref "U2") (pin "39_6") (pinfunction "GND_39_6") (pintype "power_in"))
      (node (ref "U2") (pin "39_7") (pinfunction "GND_39_7") (pintype "power_in"))
      (node (ref "U2") (pin "39_8") (pinfunction "GND_39_8") (pintype "power_in"))
      (node (ref "U2") (pin "39_9") (pinfunction "GND_39_9") (pintype "power_in"))
      (node (ref "U3") (pin "1") (pinfunction "ADJ/GND_1") (pintype "power_in"))
      (node (ref "U4") (pin "2") (pinfunction "C_2") (pintype "passive"))
      (node (ref "U5") (pin "2") (pinfunction "C_2") (pintype "passive"))
      (node (ref "U6") (pin "2") (pinfunction "C_2") (pintype "passive"))
      (node (ref "U7") (pin "1") (pinfunction "GND_1") (pintype "power_in"))
      (node (ref "U8") (pin "1") (pinfunction "ADJ/GND_1") (pintype "power_in"))
      (node (ref "U9") (pin "1") (pinfunction "GND_1") (pintype "power_in"))
      (node (ref "U9") (pin "15") (pinfunction "GND_15") (pintype "power_in"))
      (node (ref "U9") (pin "38") (pinfunction "GND_38") (pintype "power_in"))
      (node (ref "U9") (pin "39_1") (pinfunction "GND_39_1") (pintype "power_in"))
      (node (ref "U9") (pin "39_10") (pinfunction "GND_39_10") (pintype "power_in"))
      (node (ref "U9") (pin "39_11") (pinfunction "GND_39_11") (pintype "power_in"))
      (node (ref "U9") (pin "39_12") (pinfunction "GND_39_12") (pintype "power_in"))
      (node (ref "U9") (pin "39_13") (pinfunction "GND_39_13") (pintype "power_in"))
      (node (ref "U9") (pin "39_14") (pinfunction "GND_39_14") (pintype "power_in"))
      (node (ref "U9") (pin "39_15") (pinfunction "GND_39_15") (pintype "power_in"))
      (node (ref "U9") (pin "39_16") (pinfunction "GND_39_16") (pintype "power_in"))
      (node (ref "U9") (pin "39_17") (pinfunction "GND_39_17") (pintype "power_in"))
      (node (ref "U9") (pin "39_18") (pinfunction "GND_39_18") (pintype "power_in"))
      (node (ref "U9") (pin "39_19") (pinfunction "GND_39_19") (pintype "power_in"))
      (node (ref "U9") (pin "39_2") (pinfunction "GND_39_2") (pintype "power_in"))
      (node (ref "U9") (pin "39_20") (pinfunction "GND_39_20") (pintype "power_in"))
      (node (ref "U9") (pin "39_21") (pinfunction "GND_39_21") (pintype "power_in"))
      (node (ref "U9") (pin "39_3") (pinfunction "GND_39_3") (pintype "power_in"))
      (node (ref "U9") (pin "39_4") (pinfunction "GND_39_4") (pintype "power_in"))
      (node (ref "U9") (pin "39_5") (pinfunction "GND_39_5") (pintype "power_in"))
      (node (ref "U9") (pin "39_6") (pinfunction "GND_39_6") (pintype "power_in"))
      (node (ref "U9") (pin "39_7") (pinfunction "GND_39_7") (pintype "power_in"))
      (node (ref "U9") (pin "39_8") (pinfunction "GND_39_8") (pintype "power_in"))
      (node (ref "U9") (pin "39_9") (pinfunction "GND_39_9") (pintype "power_in"))
      (node (ref "X1") (pin "1") (pinfunction "1_1") (pintype "passive"))
      (node (ref "X4") (pin "3") (pinfunction "1_3") (pintype "passive"))
      (node (ref "X6") (pin "4") (pinfunction "1_4") (pintype "passive"))
      (node (ref "X7") (pin "2") (pinfunction "S_2") (pintype "passive"))
    )
    (net (code "18") (name "IO0") (class "Default")
      (node (ref "C11") (pin "1") (pinfunction "1_1") (pintype "passive"))
      (node (ref "Q2") (pin "3") (pinfunction "C_3") (pintype "passive"))
      (node (ref "R5") (pin "1") (pinfunction "1_1") (pintype "passive"))
      (node (ref "S2") (pin "1") (pinfunction "1_1") (pintype "passive"))
      (node (ref "U2") (pin "25") (pinfunction "IO0_25") (pintype "bidirectional"))
    )
    (net (code "19") (name "IO01") (class "Default")
      (node (ref "C18") (pin "1") (pinfunction "1_1") (pintype "passive"))
      (node (ref "Q9") (pin "3") (pinfunction "C_3") (pintype "passive"))
      (node (ref "R28") (pin "1") (pinfunction "1_1") (pintype "passive"))
      (node (ref "S4") (pin "1") (pinfunction "1_1") (pintype "passive"))
      (node (ref "U9") (pin "25") (pinfunction "IO0_25") (pintype "bidirectional"))
    )
    (net (code "20") (name "M0") (class "Default")
      (node (ref "EBYTEE220-900T22D1") (pin "M0") (pinfunction "M0_M0") (pintype "bidirectional"))
      (node (ref "EBYTEE220-900T22D1") (pin "M1") (pinfunction "M1_M1") (pintype "bidirectional"))
      (node (ref "U2") (pin "30") (pinfunction "IO18_30") (pintype "bidirectional"))
    )
    (net (code "21") (name "Net-(D1-PadA)") (class "Default")
      (node (ref "D1") (pin "A") (pinfunction "A_A") (pintype "passive"))
      (node (ref "SUPER-STEPDOWN1") (pin "+5V") (pinfunction "+5V_+5V") (pintype "bidirectional"))
    )
    (net (code "22") (name "Net-(D3-PadA)") (class "Default")
      (node (ref "D3") (pin "A") (pinfunction "A_A") (pintype "passive"))
      (node (ref "R3") (pin "1") (pinfunction "1_1") (pintype "passive"))
    )
    (net (code "23") (name "Net-(D9-PadA)") (class "Default")
      (node (ref "D9") (pin "A") (pinfunction "A_A") (pintype "passive"))
      (node (ref "R17") (pin "1") (pinfunction "1_1") (pintype "passive"))
    )
    (net (code "24") (name "Net-(D10-PadA)") (class "Default")
      (node (ref "D10") (pin "A") (pinfunction "A_A") (pintype "passive"))
      (node (ref "R18") (pin "1") (pinfunction "1_1") (pintype "passive"))
    )
    (net (code "25") (name "Net-(D11-PadA)") (class "Default")
      (node (ref "D11") (pin "A") (pinfunction "A_A") (pintype "passive"))
      (node (ref "R19") (pin "1") (pinfunction "1_1") (pintype "passive"))
    )
    (net (code "26") (name "Net-(D12-PadA)") (class "Default")
      (node (ref "D12") (pin "A") (pinfunction "A_A") (pintype "passive"))
      (node (ref "R20") (pin "1") (pinfunction "1_1") (pintype "passive"))
    )
    (net (code "27") (name "Net-(K1A-2)") (class "Default")
      (node (ref "D4") (pin "A") (pinfunction "A_A") (pintype "passive"))
      (node (ref "K1") (pin "16") (pinfunction "2_16") (pintype "passive"))
      (node (ref "Q4") (pin "3") (pinfunction "C_3") (pintype "passive"))
    )
    (net (code "28") (name "Net-(K2A-2)") (class "Default")
      (node (ref "D5") (pin "A") (pinfunction "A_A") (pintype "passive"))
      (node (ref "K2") (pin "16") (pinfunction "2_16") (pintype "passive"))
      (node (ref "Q5") (pin "3") (pinfunction "C_3") (pintype "passive"))
    )
    (net (code "29") (name "Net-(Q1-B)") (class "Default")
      (node (ref "Q1") (pin "1") (pinfunction "B_1") (pintype "passive"))
      (node (ref "R1") (pin "2") (pinfunction "2_2") (pintype "passive"))
    )
    (net (code "30") (name "Net-(Q2-B)") (class "Default")
      (node (ref "Q2") (pin "1") (pinfunction "B_1") (pintype "passive"))
      (node (ref "R2") (pin "2") (pinfunction "2_2") (pintype "passive"))
    )
    (net (code "31") (name "Net-(Q4-B)") (class "Default")
      (node (ref "Q4") (pin "1") (pinfunction "B_1") (pintype "passive"))
      (node (ref "U4") (pin "3") (pinfunction "ET_3") (pintype "passive"))
    )
    (net (code "32") (name "Net-(Q5-B)") (class "Default")
      (node (ref "Q5") (pin "1") (pinfunction "B_1") (pintype "passive"))
      (node (ref "U5") (pin "3") (pinfunction "ET_3") (pintype "passive"))
    )
    (net (code "33") (name "Net-(Q6-B)") (class "Default")
      (node (ref "Q6") (pin "1") (pinfunction "B_1") (pintype "passive"))
      (node (ref "U6") (pin "3") (pinfunction "ET_3") (pintype "passive"))
    )
    (net (code "34") (name "Net-(Q6-C)") (class "Default")
      (node (ref "D6") (pin "A") (pinfunction "A_A") (pintype "passive"))
      (node (ref "K3") (pin "A2") (pinfunction "A2_A2") (pintype "passive"))
      (node (ref "Q6") (pin "3") (pinfunction "C_3") (pintype "passive"))
    )
    (net (code "35") (name "Net-(Q8-B)") (class "Default")
      (node (ref "Q8") (pin "1") (pinfunction "B_1") (pintype "passive"))
      (node (ref "R25") (pin "2") (pinfunction "2_2") (pintype "passive"))
    )
    (net (code "36") (name "Net-(Q9-B)") (class "Default")
      (node (ref "Q9") (pin "1") (pinfunction "B_1") (pintype "passive"))
      (node (ref "R26") (pin "2") (pinfunction "2_2") (pintype "passive"))
    )
    (net (code "37") (name "Net-(U1-V3)") (class "Default")
      (node (ref "C3") (pin "1") (pinfunction "1_1") (pintype "passive"))
      (node (ref "U1") (pin "4") (pinfunction "V3_4") (pintype "power_in"))
    )
    (net (code "38") (name "Net-(U1-XI)") (class "Default")
      (node (ref "C4") (pin "2") (pinfunction "2_2") (pintype "passive"))
      (node (ref "Q3") (pin "2") (pinfunction "2_2") (pintype "passive"))
      (node (ref "U1") (pin "7") (pinfunction "XI_7") (pintype "input"))
    )
    (net (code "39") (name "Net-(U1-XO)") (class "Default")
      (node (ref "C5") (pin "2") (pinfunction "2_2") (pintype "passive"))
      (node (ref "Q3") (pin "1") (pinfunction "1_1") (pintype "passive"))
      (node (ref "U1") (pin "8") (pinfunction "XO_8") (pintype "output"))
    )
    (net (code "40") (name "Net-(U4-A)") (class "Default")
      (node (ref "R11") (pin "1") (pinfunction "1_1") (pintype "passive"))
      (node (ref "U4") (pin "1") (pinfunction "A_1") (pintype "passive"))
    )
    (net (code "41") (name "Net-(U4-CT)") (class "Default")
      (node (ref "R12") (pin "2") (pinfunction "2_2") (pintype "passive"))
      (node (ref "U4") (pin "4") (pinfunction "CT_4") (pintype "passive"))
    )
    (net (code "42") (name "Net-(U5-A)") (class "Default")
      (node (ref "R13") (pin "1") (pinfunction "1_1") (pintype "passive"))
      (node (ref "U5") (pin "1") (pinfunction "A_1") (pintype "passive"))
    )
    (net (code "43") (name "Net-(U5-CT)") (class "Default")
      (node (ref "R14") (pin "2") (pinfunction "2_2") (pintype "passive"))
      (node (ref "U5") (pin "4") (pinfunction "CT_4") (pintype "passive"))
    )
    (net (code "44") (name "Net-(U6-A)") (class "Default")
      (node (ref "R23") (pin "1") (pinfunction "1_1") (pintype "passive"))
      (node (ref "U6") (pin "1") (pinfunction "A_1") (pintype "passive"))
    )
    (net (code "45") (name "Net-(U6-CT)") (class "Default")
      (node (ref "R24") (pin "2") (pinfunction "2_2") (pintype "passive"))
      (node (ref "U6") (pin "4") (pinfunction "CT_4") (pintype "passive"))
    )
    (net (code "46") (name "Net-(U7-V3)") (class "Default")
      (node (ref "C16") (pin "1") (pinfunction "1_1") (pintype "passive"))
      (node (ref "U7") (pin "4") (pinfunction "V3_4") (pintype "power_in"))
    )
    (net (code "47") (name "Net-(U7-XI)") (class "Default")
      (node (ref "C12") (pin "2") (pinfunction "2_2") (pintype "passive"))
      (node (ref "Q7") (pin "2") (pinfunction "2_2") (pintype "passive"))
      (node (ref "U7") (pin "7") (pinfunction "XI_7") (pintype "input"))
    )
    (net (code "48") (name "Net-(U7-XO)") (class "Default")
      (node (ref "C13") (pin "2") (pinfunction "2_2") (pintype "passive"))
      (node (ref "Q7") (pin "1") (pinfunction "1_1") (pintype "passive"))
      (node (ref "U7") (pin "8") (pinfunction "XO_8") (pintype "output"))
    )
    (net (code "49") (name "Net-(X7A-S)") (class "Default")
      (node (ref "MODUL-BATT1") (pin "BATT+") (pinfunction "BATT+_BATT+") (pintype "bidirectional"))
      (node (ref "X7") (pin "1") (pinfunction "S_1") (pintype "passive"))
    )
    (net (code "50") (name "OUT+") (class "Default")
      (node (ref "ADS1") (pin "VDD") (pinfunction "VDD_VDD") (pintype "bidirectional"))
      (node (ref "ADS2") (pin "VDD") (pinfunction "VDD_VDD") (pintype "bidirectional"))
      (node (ref "C19") (pin "1") (pinfunction "1_1") (pintype "passive"))
      (node (ref "C21") (pin "1") (pinfunction "1_1") (pintype "passive"))
      (node (ref "C6") (pin "+") (pinfunction "+_+") (pintype "passive"))
      (node (ref "C7") (pin "1") (pinfunction "1_1") (pintype "passive"))
      (node (ref "C8") (pin "1") (pinfunction "1_1") (pintype "passive"))
      (node (ref "D1") (pin "C") (pinfunction "K_C") (pintype "passive"))
      (node (ref "D2") (pin "C") (pinfunction "K_C") (pintype "passive"))
      (node (ref "D4") (pin "C") (pinfunction "K_C") (pintype "passive"))
      (node (ref "D5") (pin "C") (pinfunction "K_C") (pintype "passive"))
      (node (ref "D6") (pin "C") (pinfunction "K_C") (pintype "passive"))
      (node (ref "D7") (pin "C") (pinfunction "K_C") (pintype "passive"))
      (node (ref "D8") (pin "C") (pinfunction "K_C") (pintype "passive"))
      (node (ref "EBYTEE220-900T22D1") (pin "VCC") (pinfunction "VCC_VCC") (pintype "bidirectional"))
      (node (ref "K1") (pin "1") (pinfunction "1_1") (pintype "passive"))
      (node (ref "K2") (pin "1") (pinfunction "1_1") (pintype "passive"))
      (node (ref "K3") (pin "A1") (pinfunction "A1_A1") (pintype "passive"))
      (node (ref "MODUL-BATT1") (pin "IN+") (pinfunction "IN+_IN+") (pintype "bidirectional"))
      (node (ref "NEO-6MGPS1") (pin "5V") (pinfunction "5V_5V") (pintype "bidirectional"))
      (node (ref "R12") (pin "1") (pinfunction "1_1") (pintype "passive"))
      (node (ref "R14") (pin "1") (pinfunction "1_1") (pintype "passive"))
      (node (ref "R24") (pin "1") (pinfunction "1_1") (pintype "passive"))
      (node (ref "R3") (pin "2") (pinfunction "2_2") (pintype "passive"))
      (node (ref "U10") (pin "8") (pinfunction "VDD_8") (pintype "power_in"))
      (node (ref "U3") (pin "3") (pinfunction "VIN_3") (pintype "input"))
      (node (ref "U8") (pin "3") (pinfunction "VIN_3") (pintype "input"))
      (node (ref "X6") (pin "1") (pinfunction "1_1") (pintype "passive"))
    )
    (net (code "51") (name "OUT-BATT") (class "Default")
      (node (ref "D8") (pin "A") (pinfunction "A_A") (pintype "passive"))
      (node (ref "MODUL-BATT1") (pin "OUT+") (pinfunction "OUT+_OUT+") (pintype "bidirectional"))
    )
    (net (code "52") (name "OUT1") (class "Default")
      (node (ref "SV1") (pin "1") (pinfunction "1_1") (pintype "passive"))
      (node (ref "U9") (pin "37") (pinfunction "IO23_37") (pintype "bidirectional"))
    )
    (net (code "53") (name "OUT2") (class "Default")
      (node (ref "SV1") (pin "2") (pinfunction "2_2") (pintype "passive"))
      (node (ref "U9") (pin "26") (pinfunction "IO4_26") (pintype "bidirectional"))
    )
    (net (code "54") (name "OUT3") (class "Default")
      (node (ref "SV1") (pin "3") (pinfunction "3_3") (pintype "passive"))
      (node (ref "U9") (pin "23") (pinfunction "IO15_23") (pintype "bidirectional"))
    )
    (net (code "55") (name "OUT4") (class "Default")
      (node (ref "SV1") (pin "4") (pinfunction "4_4") (pintype "passive"))
      (node (ref "U9") (pin "16") (pinfunction "IO13_16") (pintype "bidirectional"))
    )
    (net (code "56") (name "OUT5") (class "Default")
      (node (ref "SV1") (pin "5") (pinfunction "5_5") (pintype "passive"))
      (node (ref "U9") (pin "14") (pinfunction "IO12_14") (pintype "bidirectional"))
    )
    (net (code "57") (name "OUT6") (class "Default")
      (node (ref "SV1") (pin "6") (pinfunction "6_6") (pintype "passive"))
      (node (ref "U9") (pin "13") (pinfunction "IO14_13") (pintype "bidirectional"))
    )
    (net (code "58") (name "OUT7") (class "Default")
      (node (ref "SV1") (pin "7") (pinfunction "7_7") (pintype "passive"))
      (node (ref "U9") (pin "12") (pinfunction "IO27_12") (pintype "bidirectional"))
    )
    (net (code "59") (name "OUT8") (class "Default")
      (node (ref "SV1") (pin "8") (pinfunction "8_8") (pintype "passive"))
      (node (ref "U9") (pin "9") (pinfunction "IO33_9") (pintype "bidirectional"))
    )
    (net (code "60") (name "OUT9") (class "Default")
      (node (ref "SV1") (pin "9") (pinfunction "9_9") (pintype "passive"))
      (node (ref "U9") (pin "8") (pinfunction "IO32_8") (pintype "bidirectional"))
    )
    (net (code "61") (name "PB-PWR") (class "Default")
      (node (ref "R9") (pin "2") (pinfunction "2_2") (pintype "passive"))
      (node (ref "X3") (pin "3") (pinfunction "1_3") (pintype "passive"))
    )
    (net (code "62") (name "RTS") (class "Default")
      (node (ref "Q1") (pin "2") (pinfunction "E_2") (pintype "passive"))
      (node (ref "R2") (pin "1") (pinfunction "1_1") (pintype "passive"))
      (node (ref "U1") (pin "14") (pinfunction "~{RTS}_14") (pintype "output"))
    )
    (net (code "63") (name "RTS1") (class "Default")
      (node (ref "Q8") (pin "2") (pinfunction "E_2") (pintype "passive"))
      (node (ref "R26") (pin "1") (pinfunction "1_1") (pintype "passive"))
      (node (ref "U7") (pin "14") (pinfunction "~{RTS}_14") (pintype "output"))
    )
    (net (code "64") (name "RX") (class "Default")
      (node (ref "D10") (pin "C") (pinfunction "C_C") (pintype "passive"))
      (node (ref "U1") (pin "3") (pinfunction "RXD_3") (pintype "input"))
      (node (ref "U2") (pin "35") (pinfunction "TXD0_35") (pintype "bidirectional"))
    )
    (net (code "65") (name "RX1") (class "Default")
      (node (ref "D12") (pin "C") (pinfunction "C_C") (pintype "passive"))
      (node (ref "U7") (pin "3") (pinfunction "RXD_3") (pintype "input"))
      (node (ref "U9") (pin "35") (pinfunction "TXD0_35") (pintype "bidirectional"))
    )
    (net (code "66") (name "RXLORA_CONFIG") (class "Default")
      (node (ref "K1") (pin "S1") (pinfunction "S_S1") (pintype "passive"))
      (node (ref "X4") (pin "2") (pinfunction "1_2") (pintype "passive"))
    )
    (net (code "67") (name "RXLORA_MICRO") (class "Default")
      (node (ref "K1") (pin "O1") (pinfunction "O_O1") (pintype "passive"))
      (node (ref "U2") (pin "28") (pinfunction "IO17_28") (pintype "bidirectional"))
    )
    (net (code "68") (name "RX_GPS") (class "Default")
      (node (ref "NEO-6MGPS1") (pin "RX") (pinfunction "RX_RX") (pintype "bidirectional"))
      (node (ref "U9") (pin "31") (pinfunction "IO19_31") (pintype "bidirectional"))
    )
    (net (code "69") (name "RX_LORA") (class "Default")
      (node (ref "EBYTEE220-900T22D1") (pin "RXD") (pinfunction "RXD_RXD") (pintype "bidirectional"))
      (node (ref "K1") (pin "P1") (pinfunction "P_P1") (pintype "passive"))
    )
    (net (code "70") (name "RX_MICRO") (class "Default")
      (node (ref "U2") (pin "13") (pinfunction "IO14_13") (pintype "bidirectional"))
      (node (ref "U9") (pin "27") (pinfunction "IO16_27") (pintype "bidirectional"))
    )
    (net (code "71") (name "SCL") (class "Default")
      (node (ref "ADS1") (pin "SCL") (pinfunction "SCL_SCL") (pintype "bidirectional"))
      (node (ref "U10") (pin "10") (pinfunction "SCL_10") (pintype "input"))
      (node (ref "U2") (pin "36") (pinfunction "IO22_36") (pintype "bidirectional"))
      (node (ref "X6") (pin "3") (pinfunction "1_3") (pintype "passive"))
    )
    (net (code "72") (name "SCL1") (class "Default")
      (node (ref "ADS2") (pin "SCL") (pinfunction "SCL_SCL") (pintype "bidirectional"))
      (node (ref "U9") (pin "36") (pinfunction "IO22_36") (pintype "bidirectional"))
    )
    (net (code "73") (name "SDA") (class "Default")
      (node (ref "ADS1") (pin "SDA") (pinfunction "SDA_SDA") (pintype "bidirectional"))
      (node (ref "U10") (pin "9") (pinfunction "SDA_9") (pintype "bidirectional"))
      (node (ref "U2") (pin "33") (pinfunction "IO21_33") (pintype "bidirectional"))
      (node (ref "X6") (pin "2") (pinfunction "1_2") (pintype "passive"))
    )
    (net (code "74") (name "SDA1") (class "Default")
      (node (ref "ADS2") (pin "SDA") (pinfunction "SDA_SDA") (pintype "bidirectional"))
      (node (ref "U9") (pin "33") (pinfunction "IO21_33") (pintype "bidirectional"))
    )
    (net (code "75") (name "TX") (class "Default")
      (node (ref "D9") (pin "C") (pinfunction "C_C") (pintype "passive"))
      (node (ref "U1") (pin "2") (pinfunction "TXD_2") (pintype "output"))
      (node (ref "U2") (pin "34") (pinfunction "RXD0_34") (pintype "bidirectional"))
    )
    (net (code "76") (name "TX1") (class "Default")
      (node (ref "D11") (pin "C") (pinfunction "C_C") (pintype "passive"))
      (node (ref "U7") (pin "2") (pinfunction "TXD_2") (pintype "output"))
      (node (ref "U9") (pin "34") (pinfunction "RXD0_34") (pintype "bidirectional"))
    )
    (net (code "77") (name "TXLORA_CONFIG") (class "Default")
      (node (ref "K1") (pin "S2") (pinfunction "S_S2") (pintype "passive"))
      (node (ref "X4") (pin "1") (pinfunction "1_1") (pintype "passive"))
    )
    (net (code "78") (name "TXLORA_MICRO") (class "Default")
      (node (ref "K1") (pin "O2") (pinfunction "O_O2") (pintype "passive"))
      (node (ref "U2") (pin "27") (pinfunction "IO16_27") (pintype "bidirectional"))
    )
    (net (code "79") (name "TX_GPS") (class "Default")
      (node (ref "NEO-6MGPS1") (pin "TX") (pinfunction "TX_TX") (pintype "bidirectional"))
      (node (ref "U9") (pin "30") (pinfunction "IO18_30") (pintype "bidirectional"))
    )
    (net (code "80") (name "TX_LORA") (class "Default")
      (node (ref "EBYTEE220-900T22D1") (pin "TXD") (pinfunction "TXD_TXD") (pintype "bidirectional"))
      (node (ref "K1") (pin "P2") (pinfunction "P_P2") (pintype "passive"))
    )
    (net (code "81") (name "TX_MICRO") (class "Default")
      (node (ref "U2") (pin "23") (pinfunction "IO15_23") (pintype "bidirectional"))
      (node (ref "U9") (pin "28") (pinfunction "IO17_28") (pintype "bidirectional"))
    )
    (net (code "82") (name "USB1_N") (class "Default")
      (node (ref "J2") (pin "2") (pinfunction "D-_2") (pintype "passive"))
      (node (ref "U7") (pin "6") (pinfunction "UD-_6") (pintype "bidirectional"))
    )
    (net (code "83") (name "USB1_P") (class "Default")
      (node (ref "J2") (pin "3") (pinfunction "D+_3") (pintype "passive"))
      (node (ref "U7") (pin "5") (pinfunction "UD+_5") (pintype "bidirectional"))
    )
    (net (code "84") (name "USB_N") (class "Default")
      (node (ref "J1") (pin "2") (pinfunction "D-_2") (pintype "passive"))
      (node (ref "U1") (pin "6") (pinfunction "UD-_6") (pintype "bidirectional"))
    )
    (net (code "85") (name "USB_P") (class "Default")
      (node (ref "J1") (pin "3") (pinfunction "D+_3") (pintype "passive"))
      (node (ref "U1") (pin "5") (pinfunction "UD+_5") (pintype "bidirectional"))
    )
    (net (code "86") (name "VALVE") (class "Default")
      (node (ref "R13") (pin "2") (pinfunction "2_2") (pintype "passive"))
      (node (ref "U2") (pin "37") (pinfunction "IO23_37") (pintype "bidirectional"))
    )
    (net (code "87") (name "VALVE1") (class "Default")
      (node (ref "K2") (pin "S1") (pinfunction "S_S1") (pintype "passive"))
      (node (ref "X5") (pin "2") (pinfunction "1_2") (pintype "passive"))
    )
    (net (code "88") (name "VALVE2") (class "Default")
      (node (ref "K2") (pin "P1") (pinfunction "P_P1") (pintype "passive"))
      (node (ref "X5") (pin "1") (pinfunction "1_1") (pintype "passive"))
    )
    (net (code "89") (name "VCC") (class "Default")
      (node (ref "C9") (pin "1") (pinfunction "1_1") (pintype "passive"))
      (node (ref "R10") (pin "2") (pinfunction "2_2") (pintype "passive"))
      (node (ref "R17") (pin "2") (pinfunction "2_2") (pintype "passive"))
      (node (ref "R18") (pin "2") (pinfunction "2_2") (pintype "passive"))
      (node (ref "R4") (pin "2") (pinfunction "2_2") (pintype "passive"))
      (node (ref "R5") (pin "2") (pinfunction "2_2") (pintype "passive"))
      (node (ref "R6") (pin "2") (pinfunction "2_2") (pintype "passive"))
      (node (ref "R7") (pin "2") (pinfunction "2_2") (pintype "passive"))
      (node (ref "R8") (pin "2") (pinfunction "2_2") (pintype "passive"))
      (node (ref "U2") (pin "2") (pinfunction "3V3_2") (pintype "power_in"))
      (node (ref "U3") (pin "2") (pinfunction "VOUT_2") (pintype "output"))
      (node (ref "U3") (pin "4") (pinfunction "VOUT_4") (pintype "output"))
    )
    (net (code "90") (name "VCC1") (class "Default")
      (node (ref "C20") (pin "1") (pinfunction "1_1") (pintype "passive"))
      (node (ref "R19") (pin "2") (pinfunction "2_2") (pintype "passive"))
      (node (ref "R20") (pin "2") (pinfunction "2_2") (pintype "passive"))
      (node (ref "R27") (pin "2") (pinfunction "2_2") (pintype "passive"))
      (node (ref "R28") (pin "2") (pinfunction "2_2") (pintype "passive"))
      (node (ref "U8") (pin "2") (pinfunction "VOUT_2") (pintype "output"))
      (node (ref "U8") (pin "4") (pinfunction "VOUT_4") (pintype "output"))
      (node (ref "U9") (pin "2") (pinfunction "3V3_2") (pintype "power_in"))
    )
    (net (code "91") (name "VUSB") (class "Default")
      (node (ref "C1") (pin "1") (pinfunction "1_1") (pintype "passive"))
      (node (ref "C2") (pin "+") (pinfunction "+_+") (pintype "passive"))
      (node (ref "D2") (pin "A") (pinfunction "A_A") (pintype "passive"))
      (node (ref "J1") (pin "1") (pinfunction "VUSB_1") (pintype "passive"))
      (node (ref "U1") (pin "16") (pinfunction "VCC_16") (pintype "power_in"))
    )
    (net (code "92") (name "VUSB1") (class "Default")
      (node (ref "C14") (pin "1") (pinfunction "1_1") (pintype "passive"))
      (node (ref "C15") (pin "+") (pinfunction "+_+") (pintype "passive"))
      (node (ref "D7") (pin "A") (pinfunction "A_A") (pintype "passive"))
      (node (ref "J2") (pin "1") (pinfunction "VUSB_1") (pintype "passive"))
      (node (ref "U7") (pin "16") (pinfunction "VCC_16") (pintype "power_in"))
    )
    (net (code "93") (name "unconnected-(ADS1-PadALRT)") (class "Default")
      (node (ref "ADS1") (pin "ALRT") (pinfunction "ALRT_ALRT") (pintype "bidirectional"))
    )
    (net (code "94") (name "unconnected-(ADS2-PadA1)") (class "Default")
      (node (ref "ADS2") (pin "A1") (pinfunction "A1_A1") (pintype "bidirectional"))
    )
    (net (code "95") (name "unconnected-(ADS2-PadA2)") (class "Default")
      (node (ref "ADS2") (pin "A2") (pinfunction "A2_A2") (pintype "bidirectional"))
    )
    (net (code "96") (name "unconnected-(ADS2-PadA3)") (class "Default")
      (node (ref "ADS2") (pin "A3") (pinfunction "A3_A3") (pintype "bidirectional"))
    )
    (net (code "97") (name "unconnected-(ADS2-PadALRT)") (class "Default")
      (node (ref "ADS2") (pin "ALRT") (pinfunction "ALRT_ALRT") (pintype "bidirectional"))
    )
    (net (code "98") (name "unconnected-(EBYTEE220-900T22D1-PadAUX)") (class "Default")
      (node (ref "EBYTEE220-900T22D1") (pin "AUX") (pinfunction "AUX_AUX") (pintype "bidirectional"))
    )
    (net (code "99") (name "unconnected-(J1-ID-Pad4)") (class "Default")
      (node (ref "J1") (pin "4") (pinfunction "ID_4") (pintype "passive"))
    )
    (net (code "100") (name "unconnected-(J2-ID-Pad4)") (class "Default")
      (node (ref "J2") (pin "4") (pinfunction "ID_4") (pintype "passive"))
    )
    (net (code "101") (name "unconnected-(K2B-O-PadO1)") (class "Default")
      (node (ref "K2") (pin "O1") (pinfunction "O_O1") (pintype "passive"))
    )
    (net (code "102") (name "unconnected-(K2C-O-PadO2)") (class "Default")
      (node (ref "K2") (pin "O2") (pinfunction "O_O2") (pintype "passive"))
    )
    (net (code "103") (name "unconnected-(K2C-P-PadP2)") (class "Default")
      (node (ref "K2") (pin "P2") (pinfunction "P_P2") (pintype "passive"))
    )
    (net (code "104") (name "unconnected-(K2C-S-PadS2)") (class "Default")
      (node (ref "K2") (pin "S2") (pinfunction "S_S2") (pintype "passive"))
    )
    (net (code "105") (name "unconnected-(K3-PadNC)") (class "Default")
      (node (ref "K3") (pin "NC") (pinfunction "NC_NC") (pintype "passive"))
    )
    (net (code "106") (name "unconnected-(U1-RS232-Pad15)") (class "Default")
      (node (ref "U1") (pin "15") (pinfunction "RS232_15") (pintype "input"))
    )
    (net (code "107") (name "unconnected-(U1-~{CTS}-Pad9)") (class "Default")
      (node (ref "U1") (pin "9") (pinfunction "~{CTS}_9") (pintype "input"))
    )
    (net (code "108") (name "unconnected-(U1-~{DCD}-Pad12)") (class "Default")
      (node (ref "U1") (pin "12") (pinfunction "~{DCD}_12") (pintype "input"))
    )
    (net (code "109") (name "unconnected-(U1-~{DSR}-Pad10)") (class "Default")
      (node (ref "U1") (pin "10") (pinfunction "~{DSR}_10") (pintype "input"))
    )
    (net (code "110") (name "unconnected-(U1-~{RI}-Pad11)") (class "Default")
      (node (ref "U1") (pin "11") (pinfunction "~{RI}_11") (pintype "input"))
    )
    (net (code "111") (name "unconnected-(U2-IO2-Pad24)") (class "Default")
      (node (ref "U2") (pin "24") (pinfunction "IO2_24") (pintype "bidirectional"))
    )
    (net (code "112") (name "unconnected-(U2-IO4-Pad26)") (class "Default")
      (node (ref "U2") (pin "26") (pinfunction "IO4_26") (pintype "bidirectional"))
    )
    (net (code "113") (name "unconnected-(U2-IO12-Pad14)") (class "Default")
      (node (ref "U2") (pin "14") (pinfunction "IO12_14") (pintype "bidirectional"))
    )
    (net (code "114") (name "unconnected-(U2-IO13-Pad16)") (class "Default")
      (node (ref "U2") (pin "16") (pinfunction "IO13_16") (pintype "bidirectional"))
    )
    (net (code "115") (name "unconnected-(U2-IO19-Pad31)") (class "Default")
      (node (ref "U2") (pin "31") (pinfunction "IO19_31") (pintype "bidirectional"))
    )
    (net (code "116") (name "unconnected-(U2-IO34-Pad6)") (class "Default")
      (node (ref "U2") (pin "6") (pinfunction "IO34_6") (pintype "input"))
    )
    (net (code "117") (name "unconnected-(U2-IO35-Pad7)") (class "Default")
      (node (ref "U2") (pin "7") (pinfunction "IO35_7") (pintype "input"))
    )
    (net (code "118") (name "unconnected-(U2-SCK{slash}CLK-Pad20)") (class "Default")
      (node (ref "U2") (pin "20") (pinfunction "SCK/CLK_20") (pintype "bidirectional"))
    )
    (net (code "119") (name "unconnected-(U2-SCS{slash}CMD-Pad19)") (class "Default")
      (node (ref "U2") (pin "19") (pinfunction "SCS/CMD_19") (pintype "bidirectional"))
    )
    (net (code "120") (name "unconnected-(U2-SDI{slash}SD1-Pad22)") (class "Default")
      (node (ref "U2") (pin "22") (pinfunction "SDI/SD1_22") (pintype "bidirectional"))
    )
    (net (code "121") (name "unconnected-(U2-SDO{slash}SD0-Pad21)") (class "Default")
      (node (ref "U2") (pin "21") (pinfunction "SDO/SD0_21") (pintype "bidirectional"))
    )
    (net (code "122") (name "unconnected-(U2-SENSOR_VN-Pad5)") (class "Default")
      (node (ref "U2") (pin "5") (pinfunction "SENSOR_VN_5") (pintype "input"))
    )
    (net (code "123") (name "unconnected-(U2-SENSOR_VP-Pad4)") (class "Default")
      (node (ref "U2") (pin "4") (pinfunction "SENSOR_VP_4") (pintype "input"))
    )
    (net (code "124") (name "unconnected-(U2-SHD{slash}SD2-Pad17)") (class "Default")
      (node (ref "U2") (pin "17") (pinfunction "SHD/SD2_17") (pintype "bidirectional"))
    )
    (net (code "125") (name "unconnected-(U2-SWP{slash}SD3-Pad18)") (class "Default")
      (node (ref "U2") (pin "18") (pinfunction "SWP/SD3_18") (pintype "bidirectional"))
    )
    (net (code "126") (name "unconnected-(U7-RS232-Pad15)") (class "Default")
      (node (ref "U7") (pin "15") (pinfunction "RS232_15") (pintype "input"))
    )
    (net (code "127") (name "unconnected-(U7-~{CTS}-Pad9)") (class "Default")
      (node (ref "U7") (pin "9") (pinfunction "~{CTS}_9") (pintype "input"))
    )
    (net (code "128") (name "unconnected-(U7-~{DCD}-Pad12)") (class "Default")
      (node (ref "U7") (pin "12") (pinfunction "~{DCD}_12") (pintype "input"))
    )
    (net (code "129") (name "unconnected-(U7-~{DSR}-Pad10)") (class "Default")
      (node (ref "U7") (pin "10") (pinfunction "~{DSR}_10") (pintype "input"))
    )
    (net (code "130") (name "unconnected-(U7-~{RI}-Pad11)") (class "Default")
      (node (ref "U7") (pin "11") (pinfunction "~{RI}_11") (pintype "input"))
    )
    (net (code "131") (name "unconnected-(U9-IO2-Pad24)") (class "Default")
      (node (ref "U9") (pin "24") (pinfunction "IO2_24") (pintype "bidirectional"))
    )
    (net (code "132") (name "unconnected-(U9-IO5-Pad29)") (class "Default")
      (node (ref "U9") (pin "29") (pinfunction "IO5_29") (pintype "bidirectional"))
    )
    (net (code "133") (name "unconnected-(U9-IO25-Pad10)") (class "Default")
      (node (ref "U9") (pin "10") (pinfunction "IO25_10") (pintype "bidirectional"))
    )
    (net (code "134") (name "unconnected-(U9-IO26-Pad11)") (class "Default")
      (node (ref "U9") (pin "11") (pinfunction "IO26_11") (pintype "bidirectional"))
    )
    (net (code "135") (name "unconnected-(U9-IO34-Pad6)") (class "Default")
      (node (ref "U9") (pin "6") (pinfunction "IO34_6") (pintype "input"))
    )
    (net (code "136") (name "unconnected-(U9-IO35-Pad7)") (class "Default")
      (node (ref "U9") (pin "7") (pinfunction "IO35_7") (pintype "input"))
    )
    (net (code "137") (name "unconnected-(U9-SCK{slash}CLK-Pad20)") (class "Default")
      (node (ref "U9") (pin "20") (pinfunction "SCK/CLK_20") (pintype "bidirectional"))
    )
    (net (code "138") (name "unconnected-(U9-SCS{slash}CMD-Pad19)") (class "Default")
      (node (ref "U9") (pin "19") (pinfunction "SCS/CMD_19") (pintype "bidirectional"))
    )
    (net (code "139") (name "unconnected-(U9-SDI{slash}SD1-Pad22)") (class "Default")
      (node (ref "U9") (pin "22") (pinfunction "SDI/SD1_22") (pintype "bidirectional"))
    )
    (net (code "140") (name "unconnected-(U9-SDO{slash}SD0-Pad21)") (class "Default")
      (node (ref "U9") (pin "21") (pinfunction "SDO/SD0_21") (pintype "bidirectional"))
    )
    (net (code "141") (name "unconnected-(U9-SENSOR_VN-Pad5)") (class "Default")
      (node (ref "U9") (pin "5") (pinfunction "SENSOR_VN_5") (pintype "input"))
    )
    (net (code "142") (name "unconnected-(U9-SENSOR_VP-Pad4)") (class "Default")
      (node (ref "U9") (pin "4") (pinfunction "SENSOR_VP_4") (pintype "input"))
    )
    (net (code "143") (name "unconnected-(U9-SHD{slash}SD2-Pad17)") (class "Default")
      (node (ref "U9") (pin "17") (pinfunction "SHD/SD2_17") (pintype "bidirectional"))
    )
    (net (code "144") (name "unconnected-(U9-SWP{slash}SD3-Pad18)") (class "Default")
      (node (ref "U9") (pin "18") (pinfunction "SWP/SD3_18") (pintype "bidirectional"))
    )
    (net (code "145") (name "unconnected-(U10-AIN1-Pad5)") (class "Default")
      (node (ref "U10") (pin "5") (pinfunction "AIN1_5") (pintype "input"))
    )
    (net (code "146") (name "unconnected-(U10-AIN2-Pad6)") (class "Default")
      (node (ref "U10") (pin "6") (pinfunction "AIN2_6") (pintype "input"))
    )
    (net (code "147") (name "unconnected-(U10-AIN3-Pad7)") (class "Default")
      (node (ref "U10") (pin "7") (pinfunction "AIN3_7") (pintype "input"))
    )
    (net (code "148") (name "unconnected-(U10-ALERT{slash}RDY-Pad2)") (class "Default")
      (node (ref "U10") (pin "2") (pinfunction "ALERT/RDY_2") (pintype "output"))
    )
  )
)
